# USBMidiBreakout.net
KiCad netlist of a schematic drawn in EAGLE
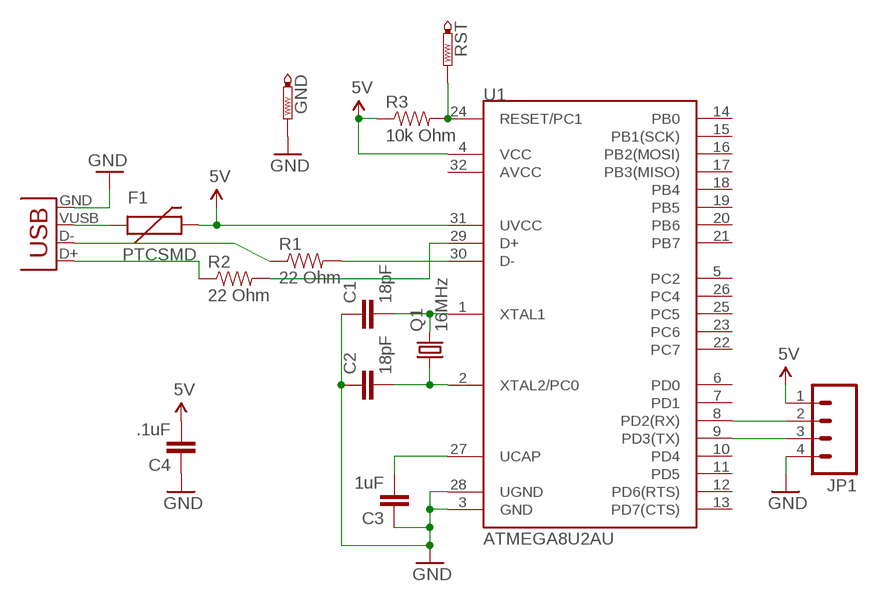
[diagram p0: schematic, sheet 1]

(export (version "E")
  (design (tool "Eeschema 10.0.6"))
  (components
    (comp (ref "C1")
      (value "18pF")
      (footprint "eagle-import:1206")
      (libsource (lib "eagle-import") (part "CAP1206"))
    )
    (comp (ref "C2")
      (value "18pF")
      (footprint "eagle-import:1206")
      (libsource (lib "eagle-import") (part "CAP1206"))
    )
    (comp (ref "C3")
      (value "1uF")
      (footprint "eagle-import:1206")
      (libsource (lib "eagle-import") (part "CAP1206"))
    )
    (comp (ref "C4")
      (value ".1uF")
      (footprint "eagle-import:1206")
      (libsource (lib "eagle-import") (part "CAP1206"))
    )
    (comp (ref "F1")
      (value "PTCSMD")
      (footprint "eagle-import:PTC-1206")
      (libsource (lib "eagle-import") (part "PTCSMD"))
    )
    (comp (ref "GND")
      (value "PTR1B1,27")
      (footprint "eagle-import:B1,27")
      (libsource (lib "eagle-import") (part "PTR1B1,27"))
    )
    (comp (ref "JP1")
      (value "M04PTH")
      (footprint "eagle-import:1X04")
      (libsource (lib "eagle-import") (part "M04PTH"))
    )
    (comp (ref "Q1")
      (value "16MHz")
      (footprint "eagle-import:HC49UP")
      (libsource (lib "eagle-import") (part "CRYSTALHC49UP"))
    )
    (comp (ref "R1")
      (value "22 Ohm")
      (footprint "eagle-import:1206")
      (libsource (lib "eagle-import") (part "RESISTOR1206"))
    )
    (comp (ref "R2")
      (value "22 Ohm")
      (footprint "eagle-import:1206")
      (libsource (lib "eagle-import") (part "RESISTOR1206"))
    )
    (comp (ref "R3")
      (value "10k Ohm")
      (footprint "eagle-import:1206")
      (libsource (lib "eagle-import") (part "RESISTOR1206"))
    )
    (comp (ref "RST")
      (value "PTR1B1,27")
      (footprint "eagle-import:B1,27")
      (libsource (lib "eagle-import") (part "PTR1B1,27"))
    )
    (comp (ref "U1")
      (value "ATMEGA8U2AU")
      (footprint "eagle-import:TQFP32-08")
      (libsource (lib "eagle-import") (part "ATMEGA8U2AU"))
    )
    (comp (ref "X1")
      (value "USB-B-S")
      (footprint "eagle-import:USB-B-SMT")
      (libsource (lib "eagle-import") (part "USB-B-S"))
    )
  )
  (nets
    (net (code "1") (name "5V") (class "Default")
      (node (ref "C4") (pin "2") (pinfunction "2_2") (pintype "passive"))
      (node (ref "F1") (pin "2") (pinfunction "2_2") (pintype "bidirectional"))
      (node (ref "JP1") (pin "1") (pinfunction "1_1") (pintype "passive"))
      (node (ref "R3") (pin "1") (pinfunction "1_1") (pintype "passive"))
      (node (ref "U1") (pin "31") (pinfunction "UVCC_31") (pintype "bidirectional"))
      (node (ref "U1") (pin "4") (pinfunction "VCC_4") (pintype "bidirectional"))
    )
    (net (code "2") (name "GND") (class "Default")
      (node (ref "C1") (pin "1") (pinfunction "1_1") (pintype "passive"))
      (node (ref "C2") (pin "1") (pinfunction "1_1") (pintype "passive"))
      (node (ref "C3") (pin "1") (pinfunction "1_1") (pintype "passive"))
      (node (ref "C4") (pin "1") (pinfunction "1_1") (pintype "passive"))
      (node (ref "GND") (pin "TP") (pinfunction "TP_TP") (pintype "input"))
      (node (ref "JP1") (pin "4") (pinfunction "4_4") (pintype "passive"))
      (node (ref "U1") (pin "28") (pinfunction "UGND_28") (pintype "bidirectional"))
      (node (ref "U1") (pin "3") (pinfunction "GND_3") (pintype "bidirectional"))
      (node (ref "X1") (pin "GND") (pinfunction "GND_GND") (pintype "bidirectional"))
    )
    (net (code "3") (name "Net-(R1-Pad1)") (class "Default")
      (node (ref "R1") (pin "1") (pinfunction "1_1") (pintype "passive"))
      (node (ref "X1") (pin "D-") (pinfunction "D-_D-") (pintype "bidirectional"))
    )
    (net (code "4") (name "Net-(R2-Pad1)") (class "Default")
      (node (ref "R2") (pin "1") (pinfunction "1_1") (pintype "passive"))
      (node (ref "X1") (pin "D+") (pinfunction "D+_D+") (pintype "bidirectional"))
    )
    (net (code "5") (name "Net-(U1-D+)") (class "Default")
      (node (ref "R2") (pin "2") (pinfunction "2_2") (pintype "passive"))
      (node (ref "U1") (pin "29") (pinfunction "D+_29") (pintype "bidirectional"))
    )
    (net (code "6") (name "Net-(U1-D-)") (class "Default")
      (node (ref "R1") (pin "2") (pinfunction "2_2") (pintype "passive"))
      (node (ref "U1") (pin "30") (pinfunction "D-_30") (pintype "bidirectional"))
    )
    (net (code "7") (name "Net-(U1-PD2(RX))") (class "Default")
      (node (ref "JP1") (pin "2") (pinfunction "2_2") (pintype "passive"))
      (node (ref "U1") (pin "8") (pinfunction "PD2(RX)_8") (pintype "bidirectional"))
    )
    (net (code "8") (name "Net-(U1-PD3(TX))") (class "Default")
      (node (ref "JP1") (pin "3") (pinfunction "3_3") (pintype "passive"))
      (node (ref "U1") (pin "9") (pinfunction "PD3(TX)_9") (pintype "bidirectional"))
    )
    (net (code "9") (name "Net-(U1-RESET{slash}PC1)") (class "Default")
      (node (ref "R3") (pin "2") (pinfunction "2_2") (pintype "passive"))
      (node (ref "RST") (pin "TP") (pinfunction "TP_TP") (pintype "input"))
      (node (ref "U1") (pin "24") (pinfunction "RESET/PC1_24") (pintype "bidirectional"))
    )
    (net (code "10") (name "Net-(U1-UCAP)") (class "Default")
      (node (ref "C3") (pin "2") (pinfunction "2_2") (pintype "passive"))
      (node (ref "U1") (pin "27") (pinfunction "UCAP_27") (pintype "bidirectional"))
    )
    (net (code "11") (name "Net-(U1-XTAL1)") (class "Default")
      (node (ref "C1") (pin "2") (pinfunction "2_2") (pintype "passive"))
      (node (ref "Q1") (pin "2") (pinfunction "2_2") (pintype "passive"))
      (node (ref "U1") (pin "1") (pinfunction "XTAL1_1") (pintype "bidirectional"))
    )
    (net (code "12") (name "Net-(U1-XTAL2{slash}PC0)") (class "Default")
      (node (ref "C2") (pin "2") (pinfunction "2_2") (pintype "passive"))
      (node (ref "Q1") (pin "1") (pinfunction "1_1") (pintype "passive"))
      (node (ref "U1") (pin "2") (pinfunction "XTAL2/PC0_2") (pintype "bidirectional"))
    )
    (net (code "13") (name "Net-(X1-VBUS)") (class "Default")
      (node (ref "F1") (pin "1") (pinfunction "1_1") (pintype "bidirectional"))
      (node (ref "X1") (pin "VUSB") (pinfunction "VBUS_VUSB") (pintype "bidirectional"))
    )
    (net (code "14") (name "unconnected-(U1-AVCC-Pad32)") (class "Default")
      (node (ref "U1") (pin "32") (pinfunction "AVCC_32") (pintype "bidirectional"))
    )
    (net (code "15") (name "unconnected-(U1-PB0-Pad14)") (class "Default")
      (node (ref "U1") (pin "14") (pinfunction "PB0_14") (pintype "bidirectional"))
    )
    (net (code "16") (name "unconnected-(U1-PB1(SCK)-Pad15)") (class "Default")
      (node (ref "U1") (pin "15") (pinfunction "PB1(SCK)_15") (pintype "bidirectional"))
    )
    (net (code "17") (name "unconnected-(U1-PB2(MOSI)-Pad16)") (class "Default")
      (node (ref "U1") (pin "16") (pinfunction "PB2(MOSI)_16") (pintype "bidirectional"))
    )
    (net (code "18") (name "unconnected-(U1-PB3(MISO)-Pad17)") (class "Default")
      (node (ref "U1") (pin "17") (pinfunction "PB3(MISO)_17") (pintype "bidirectional"))
    )
    (net (code "19") (name "unconnected-(U1-PB4-Pad18)") (class "Default")
      (node (ref "U1") (pin "18") (pinfunction "PB4_18") (pintype "bidirectional"))
    )
    (net (code "20") (name "unconnected-(U1-PB5-Pad19)") (class "Default")
      (node (ref "U1") (pin "19") (pinfunction "PB5_19") (pintype "bidirectional"))
    )
    (net (code "21") (name "unconnected-(U1-PB6-Pad20)") (class "Default")
      (node (ref "U1") (pin "20") (pinfunction "PB6_20") (pintype "bidirectional"))
    )
    (net (code "22") (name "unconnected-(U1-PB7-Pad21)") (class "Default")
      (node (ref "U1") (pin "21") (pinfunction "PB7_21") (pintype "bidirectional"))
    )
    (net (code "23") (name "unconnected-(U1-PC2-Pad5)") (class "Default")
      (node (ref "U1") (pin "5") (pinfunction "PC2_5") (pintype "bidirectional"))
    )
    (net (code "24") (name "unconnected-(U1-PC4-Pad26)") (class "Default")
      (node (ref "U1") (pin "26") (pinfunction "PC4_26") (pintype "bidirectional"))
    )
    (net (code "25") (name "unconnected-(U1-PC5-Pad25)") (class "Default")
      (node (ref "U1") (pin "25") (pinfunction "PC5_25") (pintype "bidirectional"))
    )
    (net (code "26") (name "unconnected-(U1-PC6-Pad23)") (class "Default")
      (node (ref "U1") (pin "23") (pinfunction "PC6_23") (pintype "bidirectional"))
    )
    (net (code "27") (name "unconnected-(U1-PC7-Pad22)") (class "Default")
      (node (ref "U1") (pin "22") (pinfunction "PC7_22") (pintype "bidirectional"))
    )
    (net (code "28") (name "unconnected-(U1-PD0-Pad6)") (class "Default")
      (node (ref "U1") (pin "6") (pinfunction "PD0_6") (pintype "bidirectional"))
    )
    (net (code "29") (name "unconnected-(U1-PD1-Pad7)") (class "Default")
      (node (ref "U1") (pin "7") (pinfunction "PD1_7") (pintype "bidirectional"))
    )
    (net (code "30") (name "unconnected-(U1-PD4-Pad10)") (class "Default")
      (node (ref "U1") (pin "10") (pinfunction "PD4_10") (pintype "bidirectional"))
    )
    (net (code "31") (name "unconnected-(U1-PD5-Pad11)") (class "Default")
      (node (ref "U1") (pin "11") (pinfunction "PD5_11") (pintype "bidirectional"))
    )
    (net (code "32") (name "unconnected-(U1-PD6(RTS)-Pad12)") (class "Default")
      (node (ref "U1") (pin "12") (pinfunction "PD6(RTS)_12") (pintype "bidirectional"))
    )
    (net (code "33") (name "unconnected-(U1-PD7(CTS)-Pad13)") (class "Default")
      (node (ref "U1") (pin "13") (pinfunction "PD7(CTS)_13") (pintype "bidirectional"))
    )
  )
)
